# axiom_beta_interface_dummy_v0_7.net
KiCad netlist of a schematic drawn in EAGLE
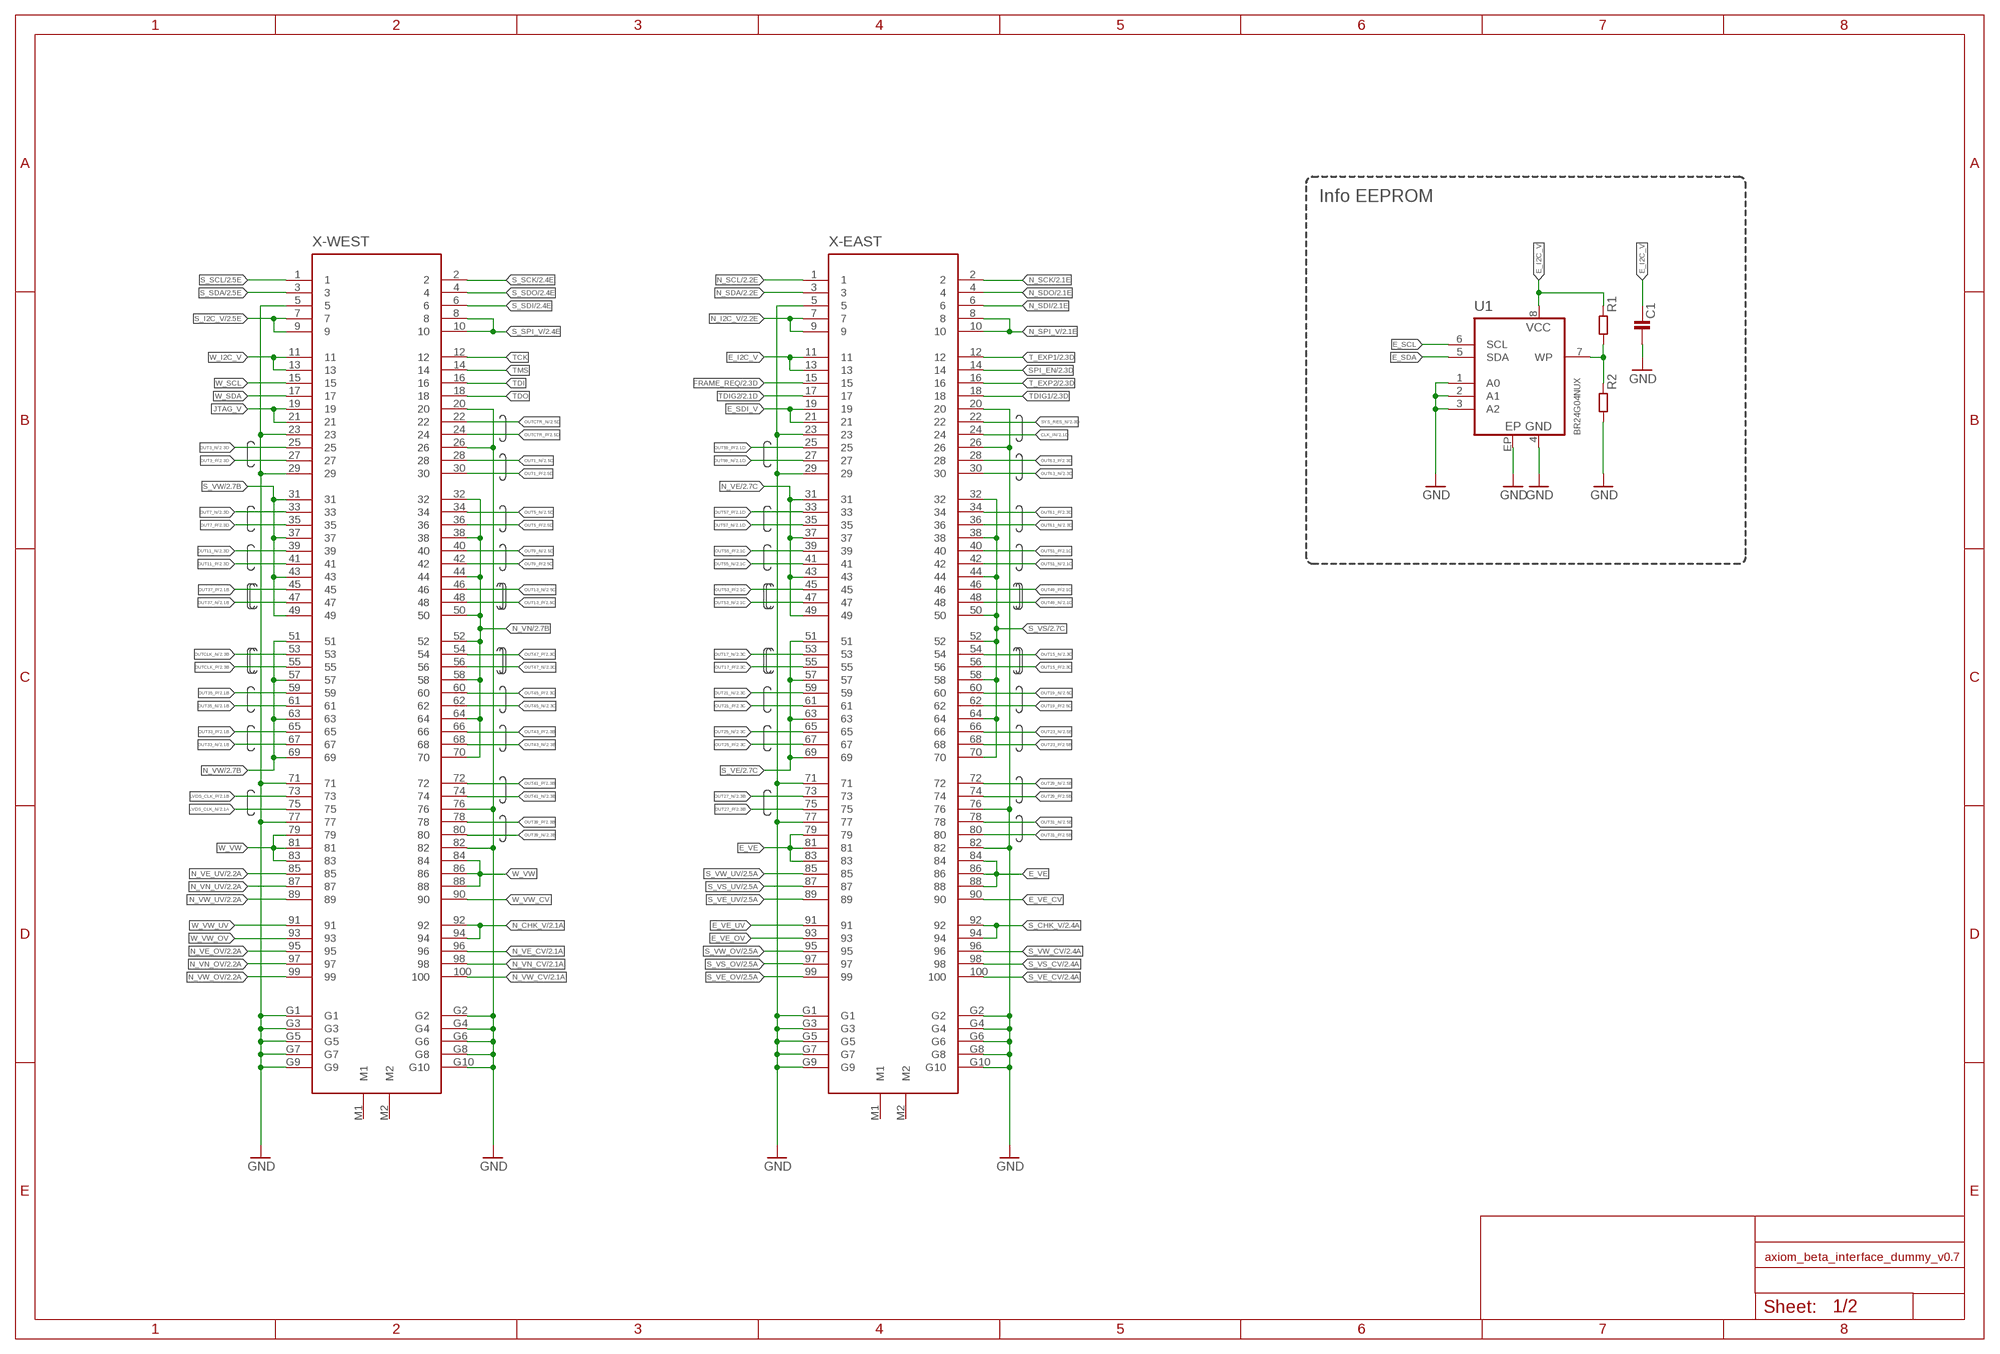
[diagram p0: schematic, sheet 1]
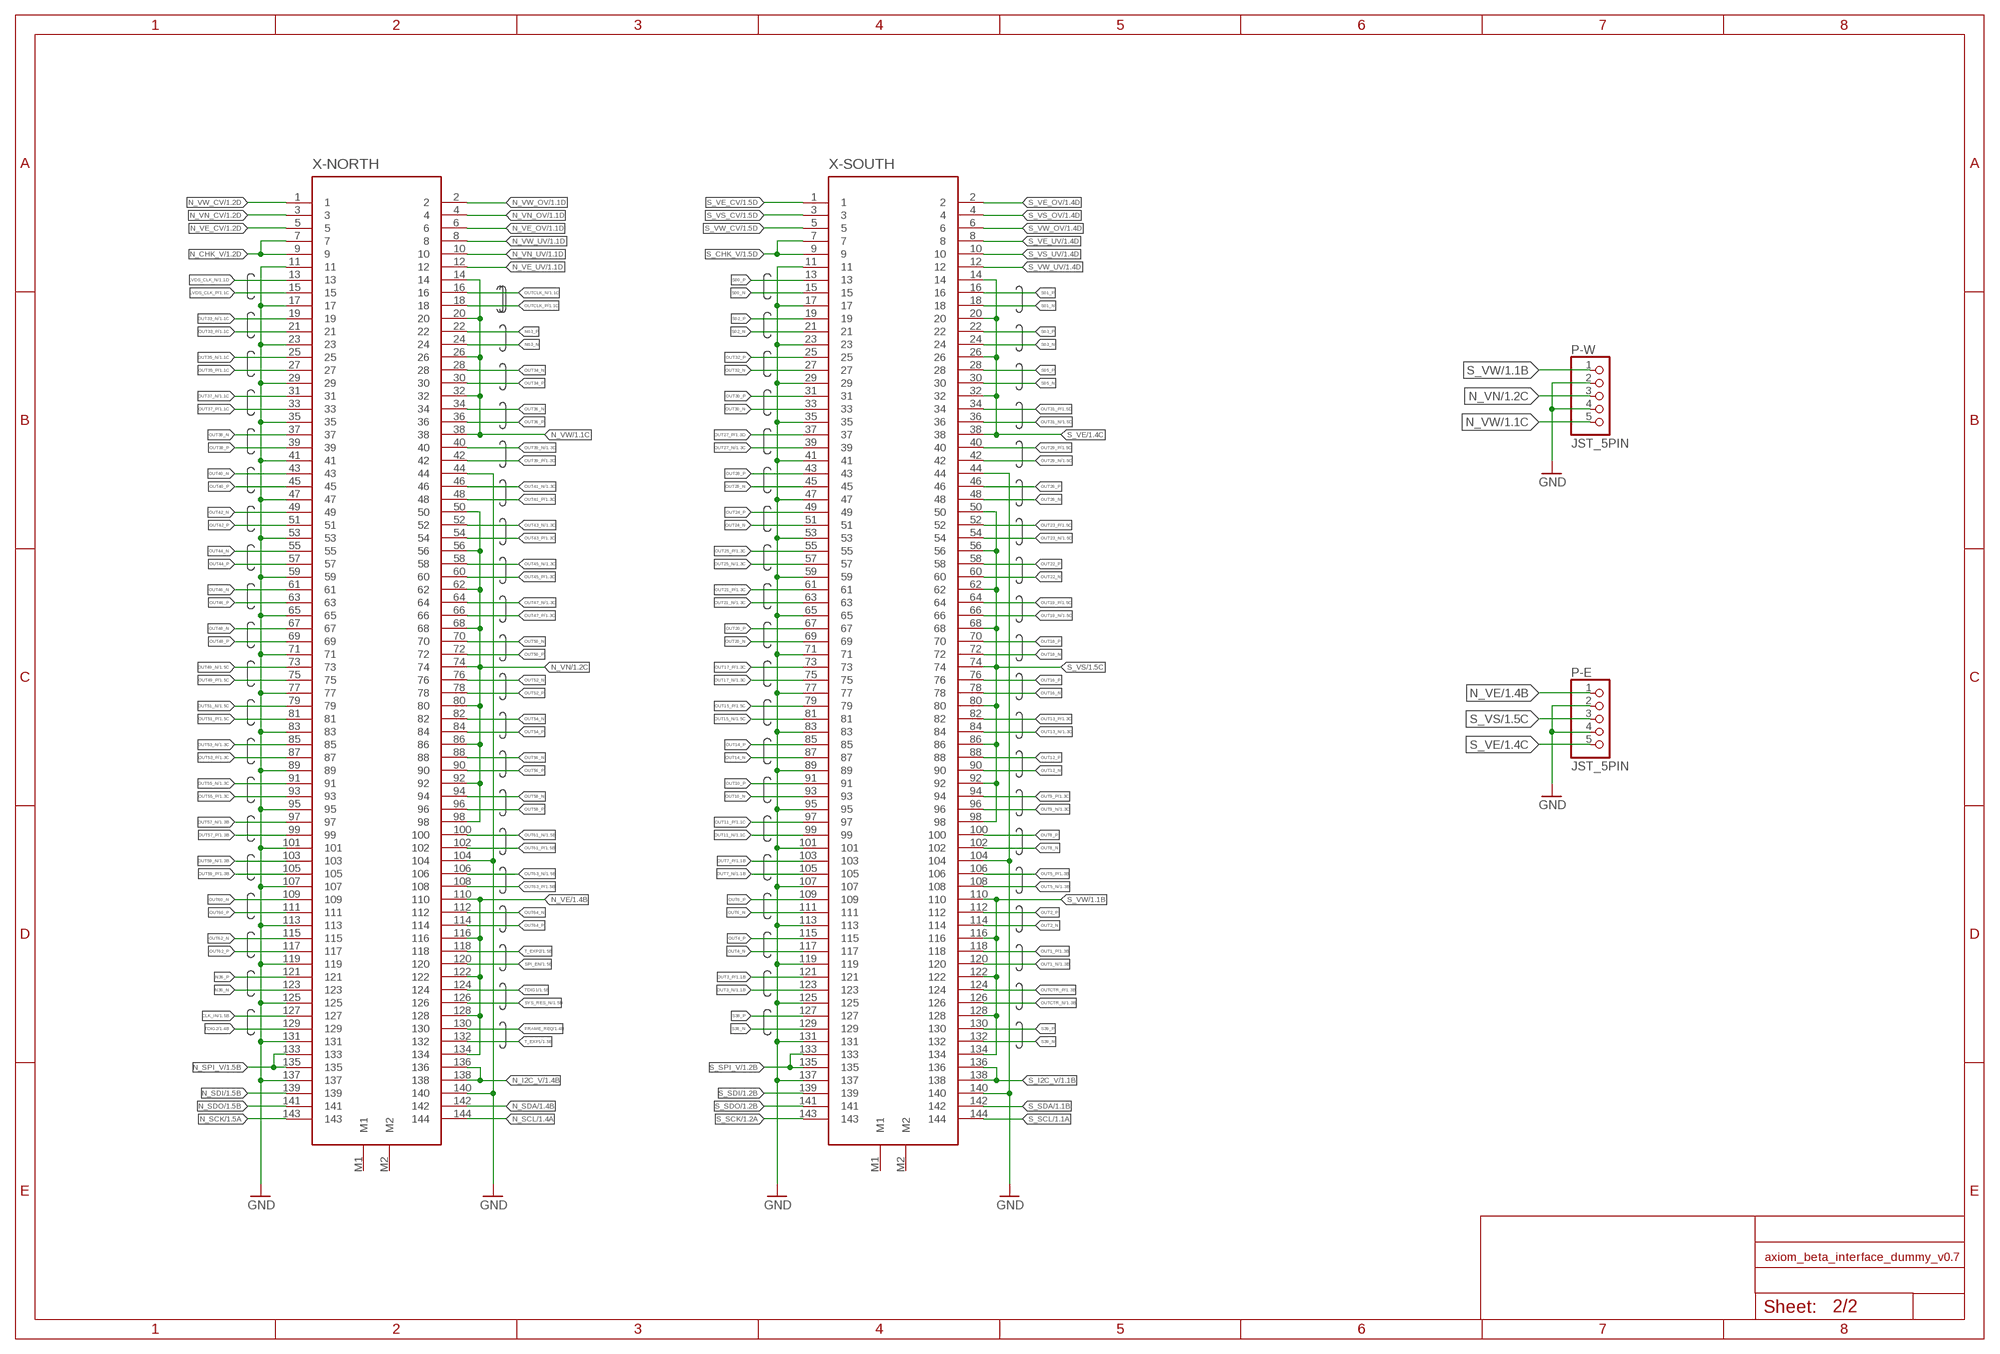
[diagram p1: schematic, sheet 2]

(export (version "E")
  (design (tool "Eeschema 10.0.6"))
  (components
    (comp (ref "P-E")
      (value "JST_5PIN")
      (footprint "eagle-import:JST-PH-5-SMT-RA")
      (libsource (lib "eagle-import") (part "JST_5PIN"))
    )
    (comp (ref "P-W")
      (value "JST_5PIN")
      (footprint "eagle-import:JST-PH-5-SMT-RA")
      (libsource (lib "eagle-import") (part "JST_5PIN"))
    )
    (comp (ref "X-NORTH")
      (value "FX10-144S")
      (footprint "eagle-import:FX10A-144S")
      (libsource (lib "eagle-import") (part "FX10-144S"))
    )
    (comp (ref "X-SOUTH")
      (value "FX10-144S")
      (footprint "eagle-import:FX10A-144S")
      (libsource (lib "eagle-import") (part "FX10-144S"))
    )
    (comp (ref "C1")
      (value "C0402-B")
      (footprint "eagle-import:0402-B")
      (libsource (lib "eagle-import") (part "C0402-B"))
    )
    (comp (ref "R1")
      (value "R0402-B")
      (footprint "eagle-import:0402-B")
      (libsource (lib "eagle-import") (part "R0402-B"))
    )
    (comp (ref "R2")
      (value "R0402-B")
      (footprint "eagle-import:0402-B")
      (libsource (lib "eagle-import") (part "R0402-B"))
    )
    (comp (ref "U1")
      (value "BR24G04NUX")
      (footprint "eagle-import:DFN200X300X100-9N")
      (libsource (lib "eagle-import") (part "BR24G04NUX"))
    )
    (comp (ref "X-EAST")
      (value "FX10-100/10P")
      (footprint "eagle-import:FX10A-100P_10")
      (libsource (lib "eagle-import") (part "FX10-100/10P"))
    )
    (comp (ref "X-WEST")
      (value "FX10-100/10P")
      (footprint "eagle-import:FX10A-100P_10")
      (libsource (lib "eagle-import") (part "FX10-100/10P"))
    )
  )
  (nets
    (net (code "1") (name "CLK_IN") (class "Default")
      (node (ref "X-EAST") (pin "24") (pinfunction "24_24") (pintype "bidirectional"))
      (node (ref "X-NORTH") (pin "127") (pinfunction "127_127") (pintype "bidirectional"))
    )
    (net (code "2") (name "E_I2C_V") (class "Default")
      (node (ref "C1") (pin "1") (pinfunction "1_1") (pintype "passive"))
      (node (ref "R1") (pin "1") (pinfunction "1_1") (pintype "passive"))
      (node (ref "U1") (pin "8") (pinfunction "VCC_8") (pintype "power_in"))
      (node (ref "X-EAST") (pin "11") (pinfunction "11_11") (pintype "bidirectional"))
      (node (ref "X-EAST") (pin "13") (pinfunction "13_13") (pintype "bidirectional"))
    )
    (net (code "3") (name "E_SCL") (class "Default")
      (node (ref "U1") (pin "6") (pinfunction "SCL_6") (pintype "input"))
    )
    (net (code "4") (name "E_SDA") (class "Default")
      (node (ref "U1") (pin "5") (pinfunction "SDA_5") (pintype "bidirectional"))
    )
    (net (code "5") (name "E_SDI_V") (class "Default")
      (node (ref "X-EAST") (pin "19") (pinfunction "19_19") (pintype "bidirectional"))
      (node (ref "X-EAST") (pin "21") (pinfunction "21_21") (pintype "bidirectional"))
    )
    (net (code "6") (name "E_VE") (class "Default")
      (node (ref "X-EAST") (pin "79") (pinfunction "79_79") (pintype "bidirectional"))
      (node (ref "X-EAST") (pin "81") (pinfunction "81_81") (pintype "bidirectional"))
      (node (ref "X-EAST") (pin "83") (pinfunction "83_83") (pintype "bidirectional"))
      (node (ref "X-EAST") (pin "84") (pinfunction "84_84") (pintype "bidirectional"))
      (node (ref "X-EAST") (pin "86") (pinfunction "86_86") (pintype "bidirectional"))
      (node (ref "X-EAST") (pin "88") (pinfunction "88_88") (pintype "bidirectional"))
    )
    (net (code "7") (name "E_VE_CV") (class "Default")
      (node (ref "X-EAST") (pin "90") (pinfunction "90_90") (pintype "bidirectional"))
    )
    (net (code "8") (name "E_VE_OV") (class "Default")
      (node (ref "X-EAST") (pin "93") (pinfunction "93_93") (pintype "bidirectional"))
    )
    (net (code "9") (name "E_VE_UV") (class "Default")
      (node (ref "X-EAST") (pin "91") (pinfunction "91_91") (pintype "bidirectional"))
    )
    (net (code "10") (name "FRAME_REQ") (class "Default")
      (node (ref "X-EAST") (pin "15") (pinfunction "15_15") (pintype "bidirectional"))
      (node (ref "X-NORTH") (pin "130") (pinfunction "130_130") (pintype "bidirectional"))
    )
    (net (code "11") (name "GND") (class "Default")
      (node (ref "C1") (pin "2") (pinfunction "2_2") (pintype "passive"))
      (node (ref "P-E") (pin "2") (pinfunction "2_2") (pintype "passive"))
      (node (ref "P-E") (pin "4") (pinfunction "4_4") (pintype "passive"))
      (node (ref "P-W") (pin "2") (pinfunction "2_2") (pintype "passive"))
      (node (ref "P-W") (pin "4") (pinfunction "4_4") (pintype "passive"))
      (node (ref "R2") (pin "2") (pinfunction "2_2") (pintype "passive"))
      (node (ref "U1") (pin "1") (pinfunction "A0_1") (pintype "input"))
      (node (ref "U1") (pin "2") (pinfunction "A1_2") (pintype "input"))
      (node (ref "U1") (pin "3") (pinfunction "A2_3") (pintype "input"))
      (node (ref "U1") (pin "4") (pinfunction "GND_4") (pintype "passive"))
      (node (ref "U1") (pin "EP") (pinfunction "EP_EP") (pintype "passive"))
      (node (ref "X-EAST") (pin "20") (pinfunction "20_20") (pintype "bidirectional"))
      (node (ref "X-EAST") (pin "23") (pinfunction "23_23") (pintype "bidirectional"))
      (node (ref "X-EAST") (pin "26") (pinfunction "26_26") (pintype "bidirectional"))
      (node (ref "X-EAST") (pin "29") (pinfunction "29_29") (pintype "bidirectional"))
      (node (ref "X-EAST") (pin "5") (pinfunction "5_5") (pintype "bidirectional"))
      (node (ref "X-EAST") (pin "71") (pinfunction "71_71") (pintype "bidirectional"))
      (node (ref "X-EAST") (pin "76") (pinfunction "76_76") (pintype "bidirectional"))
      (node (ref "X-EAST") (pin "77") (pinfunction "77_77") (pintype "bidirectional"))
      (node (ref "X-EAST") (pin "82") (pinfunction "82_82") (pintype "bidirectional"))
      (node (ref "X-EAST") (pin "G1") (pinfunction "G1_G1") (pintype "bidirectional"))
      (node (ref "X-EAST") (pin "G10") (pinfunction "G10_G10") (pintype "bidirectional"))
      (node (ref "X-EAST") (pin "G2") (pinfunction "G2_G2") (pintype "bidirectional"))
      (node (ref "X-EAST") (pin "G3") (pinfunction "G3_G3") (pintype "bidirectional"))
      (node (ref "X-EAST") (pin "G4") (pinfunction "G4_G4") (pintype "bidirectional"))
      (node (ref "X-EAST") (pin "G5") (pinfunction "G5_G5") (pintype "bidirectional"))
      (node (ref "X-EAST") (pin "G6") (pinfunction "G6_G6") (pintype "bidirectional"))
      (node (ref "X-EAST") (pin "G7") (pinfunction "G7_G7") (pintype "bidirectional"))
      (node (ref "X-EAST") (pin "G8") (pinfunction "G8_G8") (pintype "bidirectional"))
      (node (ref "X-EAST") (pin "G9") (pinfunction "G9_G9") (pintype "bidirectional"))
      (node (ref "X-NORTH") (pin "101") (pinfunction "101_101") (pintype "bidirectional"))
      (node (ref "X-NORTH") (pin "104") (pinfunction "104_104") (pintype "bidirectional"))
      (node (ref "X-NORTH") (pin "107") (pinfunction "107_107") (pintype "bidirectional"))
      (node (ref "X-NORTH") (pin "11") (pinfunction "11_11") (pintype "bidirectional"))
      (node (ref "X-NORTH") (pin "113") (pinfunction "113_113") (pintype "bidirectional"))
      (node (ref "X-NORTH") (pin "119") (pinfunction "119_119") (pintype "bidirectional"))
      (node (ref "X-NORTH") (pin "125") (pinfunction "125_125") (pintype "bidirectional"))
      (node (ref "X-NORTH") (pin "131") (pinfunction "131_131") (pintype "bidirectional"))
      (node (ref "X-NORTH") (pin "137") (pinfunction "137_137") (pintype "bidirectional"))
      (node (ref "X-NORTH") (pin "140") (pinfunction "140_140") (pintype "bidirectional"))
      (node (ref "X-NORTH") (pin "17") (pinfunction "17_17") (pintype "bidirectional"))
      (node (ref "X-NORTH") (pin "23") (pinfunction "23_23") (pintype "bidirectional"))
      (node (ref "X-NORTH") (pin "29") (pinfunction "29_29") (pintype "bidirectional"))
      (node (ref "X-NORTH") (pin "35") (pinfunction "35_35") (pintype "bidirectional"))
      (node (ref "X-NORTH") (pin "41") (pinfunction "41_41") (pintype "bidirectional"))
      (node (ref "X-NORTH") (pin "44") (pinfunction "44_44") (pintype "bidirectional"))
      (node (ref "X-NORTH") (pin "47") (pinfunction "47_47") (pintype "bidirectional"))
      (node (ref "X-NORTH") (pin "53") (pinfunction "53_53") (pintype "bidirectional"))
      (node (ref "X-NORTH") (pin "59") (pinfunction "59_59") (pintype "bidirectional"))
      (node (ref "X-NORTH") (pin "65") (pinfunction "65_65") (pintype "bidirectional"))
      (node (ref "X-NORTH") (pin "71") (pinfunction "71_71") (pintype "bidirectional"))
      (node (ref "X-NORTH") (pin "77") (pinfunction "77_77") (pintype "bidirectional"))
      (node (ref "X-NORTH") (pin "83") (pinfunction "83_83") (pintype "bidirectional"))
      (node (ref "X-NORTH") (pin "89") (pinfunction "89_89") (pintype "bidirectional"))
      (node (ref "X-NORTH") (pin "95") (pinfunction "95_95") (pintype "bidirectional"))
      (node (ref "X-SOUTH") (pin "101") (pinfunction "101_101") (pintype "bidirectional"))
      (node (ref "X-SOUTH") (pin "104") (pinfunction "104_104") (pintype "bidirectional"))
      (node (ref "X-SOUTH") (pin "107") (pinfunction "107_107") (pintype "bidirectional"))
      (node (ref "X-SOUTH") (pin "11") (pinfunction "11_11") (pintype "bidirectional"))
      (node (ref "X-SOUTH") (pin "113") (pinfunction "113_113") (pintype "bidirectional"))
      (node (ref "X-SOUTH") (pin "119") (pinfunction "119_119") (pintype "bidirectional"))
      (node (ref "X-SOUTH") (pin "125") (pinfunction "125_125") (pintype "bidirectional"))
      (node (ref "X-SOUTH") (pin "131") (pinfunction "131_131") (pintype "bidirectional"))
      (node (ref "X-SOUTH") (pin "137") (pinfunction "137_137") (pintype "bidirectional"))
      (node (ref "X-SOUTH") (pin "140") (pinfunction "140_140") (pintype "bidirectional"))
      (node (ref "X-SOUTH") (pin "17") (pinfunction "17_17") (pintype "bidirectional"))
      (node (ref "X-SOUTH") (pin "23") (pinfunction "23_23") (pintype "bidirectional"))
      (node (ref "X-SOUTH") (pin "29") (pinfunction "29_29") (pintype "bidirectional"))
      (node (ref "X-SOUTH") (pin "35") (pinfunction "35_35") (pintype "bidirectional"))
      (node (ref "X-SOUTH") (pin "41") (pinfunction "41_41") (pintype "bidirectional"))
      (node (ref "X-SOUTH") (pin "44") (pinfunction "44_44") (pintype "bidirectional"))
      (node (ref "X-SOUTH") (pin "47") (pinfunction "47_47") (pintype "bidirectional"))
      (node (ref "X-SOUTH") (pin "53") (pinfunction "53_53") (pintype "bidirectional"))
      (node (ref "X-SOUTH") (pin "59") (pinfunction "59_59") (pintype "bidirectional"))
      (node (ref "X-SOUTH") (pin "65") (pinfunction "65_65") (pintype "bidirectional"))
      (node (ref "X-SOUTH") (pin "71") (pinfunction "71_71") (pintype "bidirectional"))
      (node (ref "X-SOUTH") (pin "77") (pinfunction "77_77") (pintype "bidirectional"))
      (node (ref "X-SOUTH") (pin "83") (pinfunction "83_83") (pintype "bidirectional"))
      (node (ref "X-SOUTH") (pin "89") (pinfunction "89_89") (pintype "bidirectional"))
      (node (ref "X-SOUTH") (pin "95") (pinfunction "95_95") (pintype "bidirectional"))
      (node (ref "X-WEST") (pin "20") (pinfunction "20_20") (pintype "bidirectional"))
      (node (ref "X-WEST") (pin "23") (pinfunction "23_23") (pintype "bidirectional"))
      (node (ref "X-WEST") (pin "26") (pinfunction "26_26") (pintype "bidirectional"))
      (node (ref "X-WEST") (pin "29") (pinfunction "29_29") (pintype "bidirectional"))
      (node (ref "X-WEST") (pin "5") (pinfunction "5_5") (pintype "bidirectional"))
      (node (ref "X-WEST") (pin "71") (pinfunction "71_71") (pintype "bidirectional"))
      (node (ref "X-WEST") (pin "76") (pinfunction "76_76") (pintype "bidirectional"))
      (node (ref "X-WEST") (pin "77") (pinfunction "77_77") (pintype "bidirectional"))
      (node (ref "X-WEST") (pin "82") (pinfunction "82_82") (pintype "bidirectional"))
      (node (ref "X-WEST") (pin "G1") (pinfunction "G1_G1") (pintype "bidirectional"))
      (node (ref "X-WEST") (pin "G10") (pinfunction "G10_G10") (pintype "bidirectional"))
      (node (ref "X-WEST") (pin "G2") (pinfunction "G2_G2") (pintype "bidirectional"))
      (node (ref "X-WEST") (pin "G3") (pinfunction "G3_G3") (pintype "bidirectional"))
      (node (ref "X-WEST") (pin "G4") (pinfunction "G4_G4") (pintype "bidirectional"))
      (node (ref "X-WEST") (pin "G5") (pinfunction "G5_G5") (pintype "bidirectional"))
      (node (ref "X-WEST") (pin "G6") (pinfunction "G6_G6") (pintype "bidirectional"))
      (node (ref "X-WEST") (pin "G7") (pinfunction "G7_G7") (pintype "bidirectional"))
      (node (ref "X-WEST") (pin "G8") (pinfunction "G8_G8") (pintype "bidirectional"))
      (node (ref "X-WEST") (pin "G9") (pinfunction "G9_G9") (pintype "bidirectional"))
    )
    (net (code "12") (name "JTAG_V") (class "Default")
      (node (ref "X-WEST") (pin "19") (pinfunction "19_19") (pintype "bidirectional"))
      (node (ref "X-WEST") (pin "21") (pinfunction "21_21") (pintype "bidirectional"))
    )
    (net (code "13") (name "LVDS_CLK_N") (class "Default")
      (node (ref "X-NORTH") (pin "13") (pinfunction "13_13") (pintype "bidirectional"))
      (node (ref "X-WEST") (pin "75") (pinfunction "75_75") (pintype "bidirectional"))
    )
    (net (code "14") (name "LVDS_CLK_P") (class "Default")
      (node (ref "X-NORTH") (pin "15") (pinfunction "15_15") (pintype "bidirectional"))
      (node (ref "X-WEST") (pin "73") (pinfunction "73_73") (pintype "bidirectional"))
    )
    (net (code "15") (name "N03_N") (class "Default")
      (node (ref "X-NORTH") (pin "24") (pinfunction "24_24") (pintype "bidirectional"))
    )
    (net (code "16") (name "N03_P") (class "Default")
      (node (ref "X-NORTH") (pin "22") (pinfunction "22_22") (pintype "bidirectional"))
    )
    (net (code "17") (name "N36_N") (class "Default")
      (node (ref "X-NORTH") (pin "123") (pinfunction "123_123") (pintype "bidirectional"))
    )
    (net (code "18") (name "N36_P") (class "Default")
      (node (ref "X-NORTH") (pin "121") (pinfunction "121_121") (pintype "bidirectional"))
    )
    (net (code "19") (name "N_CHK_V") (class "Default")
      (node (ref "X-NORTH") (pin "7") (pinfunction "7_7") (pintype "bidirectional"))
      (node (ref "X-NORTH") (pin "9") (pinfunction "9_9") (pintype "bidirectional"))
      (node (ref "X-WEST") (pin "92") (pinfunction "92_92") (pintype "bidirectional"))
      (node (ref "X-WEST") (pin "94") (pinfunction "94_94") (pintype "bidirectional"))
    )
    (net (code "20") (name "N_I2C_V") (class "Default")
      (node (ref "X-EAST") (pin "7") (pinfunction "7_7") (pintype "bidirectional"))
      (node (ref "X-EAST") (pin "9") (pinfunction "9_9") (pintype "bidirectional"))
      (node (ref "X-NORTH") (pin "136") (pinfunction "136_136") (pintype "bidirectional"))
      (node (ref "X-NORTH") (pin "138") (pinfunction "138_138") (pintype "bidirectional"))
    )
    (net (code "21") (name "N_SCK") (class "Default")
      (node (ref "X-EAST") (pin "2") (pinfunction "2_2") (pintype "bidirectional"))
      (node (ref "X-NORTH") (pin "143") (pinfunction "143_143") (pintype "bidirectional"))
    )
    (net (code "22") (name "N_SCL") (class "Default")
      (node (ref "X-EAST") (pin "1") (pinfunction "1_1") (pintype "bidirectional"))
      (node (ref "X-NORTH") (pin "144") (pinfunction "144_144") (pintype "bidirectional"))
    )
    (net (code "23") (name "N_SDA") (class "Default")
      (node (ref "X-EAST") (pin "3") (pinfunction "3_3") (pintype "bidirectional"))
      (node (ref "X-NORTH") (pin "142") (pinfunction "142_142") (pintype "bidirectional"))
    )
    (net (code "24") (name "N_SDI") (class "Default")
      (node (ref "X-EAST") (pin "6") (pinfunction "6_6") (pintype "bidirectional"))
      (node (ref "X-NORTH") (pin "139") (pinfunction "139_139") (pintype "bidirectional"))
    )
    (net (code "25") (name "N_SDO") (class "Default")
      (node (ref "X-EAST") (pin "4") (pinfunction "4_4") (pintype "bidirectional"))
      (node (ref "X-NORTH") (pin "141") (pinfunction "141_141") (pintype "bidirectional"))
    )
    (net (code "26") (name "N_SPI_V") (class "Default")
      (node (ref "X-EAST") (pin "10") (pinfunction "10_10") (pintype "bidirectional"))
      (node (ref "X-EAST") (pin "8") (pinfunction "8_8") (pintype "bidirectional"))
      (node (ref "X-NORTH") (pin "133") (pinfunction "133_133") (pintype "bidirectional"))
      (node (ref "X-NORTH") (pin "135") (pinfunction "135_135") (pintype "bidirectional"))
    )
    (net (code "27") (name "N_VE") (class "Default")
      (node (ref "P-E") (pin "1") (pinfunction "1_1") (pintype "passive"))
      (node (ref "X-EAST") (pin "31") (pinfunction "31_31") (pintype "bidirectional"))
      (node (ref "X-EAST") (pin "37") (pinfunction "37_37") (pintype "bidirectional"))
      (node (ref "X-EAST") (pin "43") (pinfunction "43_43") (pintype "bidirectional"))
      (node (ref "X-EAST") (pin "49") (pinfunction "49_49") (pintype "bidirectional"))
      (node (ref "X-NORTH") (pin "110") (pinfunction "110_110") (pintype "bidirectional"))
      (node (ref "X-NORTH") (pin "116") (pinfunction "116_116") (pintype "bidirectional"))
      (node (ref "X-NORTH") (pin "122") (pinfunction "122_122") (pintype "bidirectional"))
      (node (ref "X-NORTH") (pin "128") (pinfunction "128_128") (pintype "bidirectional"))
      (node (ref "X-NORTH") (pin "134") (pinfunction "134_134") (pintype "bidirectional"))
    )
    (net (code "28") (name "N_VE_CV") (class "Default")
      (node (ref "X-NORTH") (pin "5") (pinfunction "5_5") (pintype "bidirectional"))
      (node (ref "X-WEST") (pin "96") (pinfunction "96_96") (pintype "bidirectional"))
    )
    (net (code "29") (name "N_VE_OV") (class "Default")
      (node (ref "X-NORTH") (pin "6") (pinfunction "6_6") (pintype "bidirectional"))
      (node (ref "X-WEST") (pin "95") (pinfunction "95_95") (pintype "bidirectional"))
    )
    (net (code "30") (name "N_VE_UV") (class "Default")
      (node (ref "X-NORTH") (pin "12") (pinfunction "12_12") (pintype "bidirectional"))
      (node (ref "X-WEST") (pin "85") (pinfunction "85_85") (pintype "bidirectional"))
    )
    (net (code "31") (name "N_VN") (class "Default")
      (node (ref "P-W") (pin "3") (pinfunction "3_3") (pintype "passive"))
      (node (ref "X-NORTH") (pin "50") (pinfunction "50_50") (pintype "bidirectional"))
      (node (ref "X-NORTH") (pin "56") (pinfunction "56_56") (pintype "bidirectional"))
      (node (ref "X-NORTH") (pin "62") (pinfunction "62_62") (pintype "bidirectional"))
      (node (ref "X-NORTH") (pin "68") (pinfunction "68_68") (pintype "bidirectional"))
      (node (ref "X-NORTH") (pin "74") (pinfunction "74_74") (pintype "bidirectional"))
      (node (ref "X-NORTH") (pin "80") (pinfunction "80_80") (pintype "bidirectional"))
      (node (ref "X-NORTH") (pin "86") (pinfunction "86_86") (pintype "bidirectional"))
      (node (ref "X-NORTH") (pin "92") (pinfunction "92_92") (pintype "bidirectional"))
      (node (ref "X-NORTH") (pin "98") (pinfunction "98_98") (pintype "bidirectional"))
      (node (ref "X-WEST") (pin "32") (pinfunction "32_32") (pintype "bidirectional"))
      (node (ref "X-WEST") (pin "38") (pinfunction "38_38") (pintype "bidirectional"))
      (node (ref "X-WEST") (pin "44") (pinfunction "44_44") (pintype "bidirectional"))
      (node (ref "X-WEST") (pin "50") (pinfunction "50_50") (pintype "bidirectional"))
      (node (ref "X-WEST") (pin "52") (pinfunction "52_52") (pintype "bidirectional"))
      (node (ref "X-WEST") (pin "58") (pinfunction "58_58") (pintype "bidirectional"))
      (node (ref "X-WEST") (pin "64") (pinfunction "64_64") (pintype "bidirectional"))
      (node (ref "X-WEST") (pin "70") (pinfunction "70_70") (pintype "bidirectional"))
    )
    (net (code "32") (name "N_VN_CV") (class "Default")
      (node (ref "X-NORTH") (pin "3") (pinfunction "3_3") (pintype "bidirectional"))
      (node (ref "X-WEST") (pin "98") (pinfunction "98_98") (pintype "bidirectional"))
    )
    (net (code "33") (name "N_VN_OV") (class "Default")
      (node (ref "X-NORTH") (pin "4") (pinfunction "4_4") (pintype "bidirectional"))
      (node (ref "X-WEST") (pin "97") (pinfunction "97_97") (pintype "bidirectional"))
    )
    (net (code "34") (name "N_VN_UV") (class "Default")
      (node (ref "X-NORTH") (pin "10") (pinfunction "10_10") (pintype "bidirectional"))
      (node (ref "X-WEST") (pin "87") (pinfunction "87_87") (pintype "bidirectional"))
    )
    (net (code "35") (name "N_VW") (class "Default")
      (node (ref "P-W") (pin "5") (pinfunction "5_5") (pintype "passive"))
      (node (ref "X-NORTH") (pin "14") (pinfunction "14_14") (pintype "bidirectional"))
      (node (ref "X-NORTH") (pin "20") (pinfunction "20_20") (pintype "bidirectional"))
      (node (ref "X-NORTH") (pin "26") (pinfunction "26_26") (pintype "bidirectional"))
      (node (ref "X-NORTH") (pin "32") (pinfunction "32_32") (pintype "bidirectional"))
      (node (ref "X-NORTH") (pin "38") (pinfunction "38_38") (pintype "bidirectional"))
      (node (ref "X-WEST") (pin "51") (pinfunction "51_51") (pintype "bidirectional"))
      (node (ref "X-WEST") (pin "57") (pinfunction "57_57") (pintype "bidirectional"))
      (node (ref "X-WEST") (pin "63") (pinfunction "63_63") (pintype "bidirectional"))
      (node (ref "X-WEST") (pin "69") (pinfunction "69_69") (pintype "bidirectional"))
    )
    (net (code "36") (name "N_VW_CV") (class "Default")
      (node (ref "X-NORTH") (pin "1") (pinfunction "1_1") (pintype "bidirectional"))
      (node (ref "X-WEST") (pin "100") (pinfunction "100_100") (pintype "bidirectional"))
    )
    (net (code "37") (name "N_VW_OV") (class "Default")
      (node (ref "X-NORTH") (pin "2") (pinfunction "2_2") (pintype "bidirectional"))
      (node (ref "X-WEST") (pin "99") (pinfunction "99_99") (pintype "bidirectional"))
    )
    (net (code "38") (name "N_VW_UV") (class "Default")
      (node (ref "X-NORTH") (pin "8") (pinfunction "8_8") (pintype "bidirectional"))
      (node (ref "X-WEST") (pin "89") (pinfunction "89_89") (pintype "bidirectional"))
    )
    (net (code "39") (name "Net-(U1-WP)") (class "Default")
      (node (ref "R1") (pin "2") (pinfunction "2_2") (pintype "passive"))
      (node (ref "R2") (pin "1") (pinfunction "1_1") (pintype "passive"))
      (node (ref "U1") (pin "7") (pinfunction "WP_7") (pintype "input"))
    )
    (net (code "40") (name "OUT1_N") (class "Default")
      (node (ref "X-SOUTH") (pin "120") (pinfunction "120_120") (pintype "bidirectional"))
      (node (ref "X-WEST") (pin "28") (pinfunction "28_28") (pintype "bidirectional"))
    )
    (net (code "41") (name "OUT1_P") (class "Default")
      (node (ref "X-SOUTH") (pin "118") (pinfunction "118_118") (pintype "bidirectional"))
      (node (ref "X-WEST") (pin "30") (pinfunction "30_30") (pintype "bidirectional"))
    )
    (net (code "42") (name "OUT2_N") (class "Default")
      (node (ref "X-SOUTH") (pin "114") (pinfunction "114_114") (pintype "bidirectional"))
    )
    (net (code "43") (name "OUT2_P") (class "Default")
      (node (ref "X-SOUTH") (pin "112") (pinfunction "112_112") (pintype "bidirectional"))
    )
    (net (code "44") (name "OUT3_N") (class "Default")
      (node (ref "X-SOUTH") (pin "123") (pinfunction "123_123") (pintype "bidirectional"))
      (node (ref "X-WEST") (pin "25") (pinfunction "25_25") (pintype "bidirectional"))
    )
    (net (code "45") (name "OUT3_P") (class "Default")
      (node (ref "X-SOUTH") (pin "121") (pinfunction "121_121") (pintype "bidirectional"))
      (node (ref "X-WEST") (pin "27") (pinfunction "27_27") (pintype "bidirectional"))
    )
    (net (code "46") (name "OUT4_N") (class "Default")
      (node (ref "X-SOUTH") (pin "117") (pinfunction "117_117") (pintype "bidirectional"))
    )
    (net (code "47") (name "OUT4_P") (class "Default")
      (node (ref "X-SOUTH") (pin "115") (pinfunction "115_115") (pintype "bidirectional"))
    )
    (net (code "48") (name "OUT5_N") (class "Default")
      (node (ref "X-SOUTH") (pin "108") (pinfunction "108_108") (pintype "bidirectional"))
      (node (ref "X-WEST") (pin "34") (pinfunction "34_34") (pintype "bidirectional"))
    )
    (net (code "49") (name "OUT5_P") (class "Default")
      (node (ref "X-SOUTH") (pin "106") (pinfunction "106_106") (pintype "bidirectional"))
      (node (ref "X-WEST") (pin "36") (pinfunction "36_36") (pintype "bidirectional"))
    )
    (net (code "50") (name "OUT6_N") (class "Default")
      (node (ref "X-SOUTH") (pin "111") (pinfunction "111_111") (pintype "bidirectional"))
    )
    (net (code "51") (name "OUT6_P") (class "Default")
      (node (ref "X-SOUTH") (pin "109") (pinfunction "109_109") (pintype "bidirectional"))
    )
    (net (code "52") (name "OUT7_N") (class "Default")
      (node (ref "X-SOUTH") (pin "105") (pinfunction "105_105") (pintype "bidirectional"))
      (node (ref "X-WEST") (pin "33") (pinfunction "33_33") (pintype "bidirectional"))
    )
    (net (code "53") (name "OUT7_P") (class "Default")
      (node (ref "X-SOUTH") (pin "103") (pinfunction "103_103") (pintype "bidirectional"))
      (node (ref "X-WEST") (pin "35") (pinfunction "35_35") (pintype "bidirectional"))
    )
    (net (code "54") (name "OUT8_N") (class "Default")
      (node (ref "X-SOUTH") (pin "102") (pinfunction "102_102") (pintype "bidirectional"))
    )
    (net (code "55") (name "OUT8_P") (class "Default")
      (node (ref "X-SOUTH") (pin "100") (pinfunction "100_100") (pintype "bidirectional"))
    )
    (net (code "56") (name "OUT9_N") (class "Default")
      (node (ref "X-SOUTH") (pin "96") (pinfunction "96_96") (pintype "bidirectional"))
      (node (ref "X-WEST") (pin "40") (pinfunction "40_40") (pintype "bidirectional"))
    )
    (net (code "57") (name "OUT9_P") (class "Default")
      (node (ref "X-SOUTH") (pin "94") (pinfunction "94_94") (pintype "bidirectional"))
      (node (ref "X-WEST") (pin "42") (pinfunction "42_42") (pintype "bidirectional"))
    )
    (net (code "58") (name "OUT10_N") (class "Default")
      (node (ref "X-SOUTH") (pin "93") (pinfunction "93_93") (pintype "bidirectional"))
    )
    (net (code "59") (name "OUT10_P") (class "Default")
      (node (ref "X-SOUTH") (pin "91") (pinfunction "91_91") (pintype "bidirectional"))
    )
    (net (code "60") (name "OUT11_N") (class "Default")
      (node (ref "X-SOUTH") (pin "99") (pinfunction "99_99") (pintype "bidirectional"))
      (node (ref "X-WEST") (pin "39") (pinfunction "39_39") (pintype "bidirectional"))
    )
    (net (code "61") (name "OUT11_P") (class "Default")
      (node (ref "X-SOUTH") (pin "97") (pinfunction "97_97") (pintype "bidirectional"))
      (node (ref "X-WEST") (pin "41") (pinfunction "41_41") (pintype "bidirectional"))
    )
    (net (code "62") (name "OUT12_N") (class "Default")
      (node (ref "X-SOUTH") (pin "90") (pinfunction "90_90") (pintype "bidirectional"))
    )
    (net (code "63") (name "OUT12_P") (class "Default")
      (node (ref "X-SOUTH") (pin "88") (pinfunction "88_88") (pintype "bidirectional"))
    )
    (net (code "64") (name "OUT13_N") (class "Default")
      (node (ref "X-SOUTH") (pin "84") (pinfunction "84_84") (pintype "bidirectional"))
      (node (ref "X-WEST") (pin "46") (pinfunction "46_46") (pintype "bidirectional"))
    )
    (net (code "65") (name "OUT13_P") (class "Default")
      (node (ref "X-SOUTH") (pin "82") (pinfunction "82_82") (pintype "bidirectional"))
      (node (ref "X-WEST") (pin "48") (pinfunction "48_48") (pintype "bidirectional"))
    )
    (net (code "66") (name "OUT14_N") (class "Default")
      (node (ref "X-SOUTH") (pin "87") (pinfunction "87_87") (pintype "bidirectional"))
    )
    (net (code "67") (name "OUT14_P") (class "Default")
      (node (ref "X-SOUTH") (pin "85") (pinfunction "85_85") (pintype "bidirectional"))
    )
    (net (code "68") (name "OUT15_N") (class "Default")
      (node (ref "X-EAST") (pin "54") (pinfunction "54_54") (pintype "bidirectional"))
      (node (ref "X-SOUTH") (pin "81") (pinfunction "81_81") (pintype "bidirectional"))
    )
    (net (code "69") (name "OUT15_P") (class "Default")
      (node (ref "X-EAST") (pin "56") (pinfunction "56_56") (pintype "bidirectional"))
      (node (ref "X-SOUTH") (pin "79") (pinfunction "79_79") (pintype "bidirectional"))
    )
    (net (code "70") (name "OUT16_N") (class "Default")
      (node (ref "X-SOUTH") (pin "78") (pinfunction "78_78") (pintype "bidirectional"))
    )
    (net (code "71") (name "OUT16_P") (class "Default")
      (node (ref "X-SOUTH") (pin "76") (pinfunction "76_76") (pintype "bidirectional"))
    )
    (net (code "72") (name "OUT17_N") (class "Default")
      (node (ref "X-EAST") (pin "53") (pinfunction "53_53") (pintype "bidirectional"))
      (node (ref "X-SOUTH") (pin "75") (pinfunction "75_75") (pintype "bidirectional"))
    )
    (net (code "73") (name "OUT17_P") (class "Default")
      (node (ref "X-EAST") (pin "55") (pinfunction "55_55") (pintype "bidirectional"))
      (node (ref "X-SOUTH") (pin "73") (pinfunction "73_73") (pintype "bidirectional"))
    )
    (net (code "74") (name "OUT18_N") (class "Default")
      (node (ref "X-SOUTH") (pin "72") (pinfunction "72_72") (pintype "bidirectional"))
    )
    (net (code "75") (name "OUT18_P") (class "Default")
      (node (ref "X-SOUTH") (pin "70") (pinfunction "70_70") (pintype "bidirectional"))
    )
    (net (code "76") (name "OUT19_N") (class "Default")
      (node (ref "X-EAST") (pin "60") (pinfunction "60_60") (pintype "bidirectional"))
      (node (ref "X-SOUTH") (pin "66") (pinfunction "66_66") (pintype "bidirectional"))
    )
    (net (code "77") (name "OUT19_P") (class "Default")
      (node (ref "X-EAST") (pin "62") (pinfunction "62_62") (pintype "bidirectional"))
      (node (ref "X-SOUTH") (pin "64") (pinfunction "64_64") (pintype "bidirectional"))
    )
    (net (code "78") (name "OUT20_N") (class "Default")
      (node (ref "X-SOUTH") (pin "69") (pinfunction "69_69") (pintype "bidirectional"))
    )
    (net (code "79") (name "OUT20_P") (class "Default")
      (node (ref "X-SOUTH") (pin "67") (pinfunction "67_67") (pintype "bidirectional"))
    )
    (net (code "80") (name "OUT21_N") (class "Default")
      (node (ref "X-EAST") (pin "59") (pinfunction "59_59") (pintype "bidirectional"))
      (node (ref "X-SOUTH") (pin "63") (pinfunction "63_63") (pintype "bidirectional"))
    )
    (net (code "81") (name "OUT21_P") (class "Default")
      (node (ref "X-EAST") (pin "61") (pinfunction "61_61") (pintype "bidirectional"))
      (node (ref "X-SOUTH") (pin "61") (pinfunction "61_61") (pintype "bidirectional"))
    )
    (net (code "82") (name "OUT22_N") (class "Default")
      (node (ref "X-SOUTH") (pin "60") (pinfunction "60_60") (pintype "bidirectional"))
    )
    (net (code "83") (name "OUT22_P") (class "Default")
      (node (ref "X-SOUTH") (pin "58") (pinfunction "58_58") (pintype "bidirectional"))
    )
    (net (code "84") (name "OUT23_N") (class "Default")
      (node (ref "X-EAST") (pin "66") (pinfunction "66_66") (pintype "bidirectional"))
      (node (ref "X-SOUTH") (pin "54") (pinfunction "54_54") (pintype "bidirectional"))
    )
    (net (code "85") (name "OUT23_P") (class "Default")
      (node (ref "X-EAST") (pin "68") (pinfunction "68_68") (pintype "bidirectional"))
      (node (ref "X-SOUTH") (pin "52") (pinfunction "52_52") (pintype "bidirectional"))
    )
    (net (code "86") (name "OUT24_N") (class "Default")
      (node (ref "X-SOUTH") (pin "51") (pinfunction "51_51") (pintype "bidirectional"))
    )
    (net (code "87") (name "OUT24_P") (class "Default")
      (node (ref "X-SOUTH") (pin "49") (pinfunction "49_49") (pintype "bidirectional"))
    )
    (net (code "88") (name "OUT25_N") (class "Default")
      (node (ref "X-EAST") (pin "65") (pinfunction "65_65") (pintype "bidirectional"))
      (node (ref "X-SOUTH") (pin "57") (pinfunction "57_57") (pintype "bidirectional"))
    )
    (net (code "89") (name "OUT25_P") (class "Default")
      (node (ref "X-EAST") (pin "67") (pinfunction "67_67") (pintype "bidirectional"))
      (node (ref "X-SOUTH") (pin "55") (pinfunction "55_55") (pintype "bidirectional"))
    )
    (net (code "90") (name "OUT26_N") (class "Default")
      (node (ref "X-SOUTH") (pin "48") (pinfunction "48_48") (pintype "bidirectional"))
    )
    (net (code "91") (name "OUT26_P") (class "Default")
      (node (ref "X-SOUTH") (pin "46") (pinfunction "46_46") (pintype "bidirectional"))
    )
    (net (code "92") (name "OUT27_N") (class "Default")
      (node (ref "X-EAST") (pin "73") (pinfunction "73_73") (pintype "bidirectional"))
      (node (ref "X-SOUTH") (pin "39") (pinfunction "39_39") (pintype "bidirectional"))
    )
    (net (code "93") (name "OUT27_P") (class "Default")
      (node (ref "X-EAST") (pin "75") (pinfunction "75_75") (pintype "bidirectional"))
      (node (ref "X-SOUTH") (pin "37") (pinfunction "37_37") (pintype "bidirectional"))
    )
    (net (code "94") (name "OUT28_N") (class "Default")
      (node (ref "X-SOUTH") (pin "45") (pinfunction "45_45") (pintype "bidirectional"))
    )
    (net (code "95") (name "OUT28_P") (class "Default")
      (node (ref "X-SOUTH") (pin "43") (pinfunction "43_43") (pintype "bidirectional"))
    )
    (net (code "96") (name "OUT29_N") (class "Default")
      (node (ref "X-EAST") (pin "72") (pinfunction "72_72") (pintype "bidirectional"))
      (node (ref "X-SOUTH") (pin "42") (pinfunction "42_42") (pintype "bidirectional"))
    )
    (net (code "97") (name "OUT29_P") (class "Default")
      (node (ref "X-EAST") (pin "74") (pinfunction "74_74") (pintype "bidirectional"))
      (node (ref "X-SOUTH") (pin "40") (pinfunction "40_40") (pintype "bidirectional"))
    )
    (net (code "98") (name "OUT30_N") (class "Default")
      (node (ref "X-SOUTH") (pin "33") (pinfunction "33_33") (pintype "bidirectional"))
    )
    (net (code "99") (name "OUT30_P") (class "Default")
      (node (ref "X-SOUTH") (pin "31") (pinfunction "31_31") (pintype "bidirectional"))
    )
    (net (code "100") (name "OUT31_N") (class "Default")
      (node (ref "X-EAST") (pin "78") (pinfunction "78_78") (pintype "bidirectional"))
      (node (ref "X-SOUTH") (pin "36") (pinfunction "36_36") (pintype "bidirectional"))
    )
    (net (code "101") (name "OUT31_P") (class "Default")
      (node (ref "X-EAST") (pin "80") (pinfunction "80_80") (pintype "bidirectional"))
      (node (ref "X-SOUTH") (pin "34") (pinfunction "34_34") (pintype "bidirectional"))
    )
    (net (code "102") (name "OUT32_N") (class "Default")
      (node (ref "X-SOUTH") (pin "27") (pinfunction "27_27") (pintype "bidirectional"))
    )
    (net (code "103") (name "OUT32_P") (class "Default")
      (node (ref "X-SOUTH") (pin "25") (pinfunction "25_25") (pintype "bidirectional"))
    )
    (net (code "104") (name "OUT33_N") (class "Default")
      (node (ref "X-NORTH") (pin "19") (pinfunction "19_19") (pintype "bidirectional"))
      (node (ref "X-WEST") (pin "67") (pinfunction "67_67") (pintype "bidirectional"))
    )
    (net (code "105") (name "OUT33_P") (class "Default")
      (node (ref "X-NORTH") (pin "21") (pinfunction "21_21") (pintype "bidirectional"))
      (node (ref "X-WEST") (pin "65") (pinfunction "65_65") (pintype "bidirectional"))
    )
    (net (code "106") (name "OUT34_N") (class "Default")
      (node (ref "X-NORTH") (pin "28") (pinfunction "28_28") (pintype "bidirectional"))
    )
    (net (code "107") (name "OUT34_P") (class "Default")
      (node (ref "X-NORTH") (pin "30") (pinfunction "30_30") (pintype "bidirectional"))
    )
    (net (code "108") (name "OUT35_N") (class "Default")
      (node (ref "X-NORTH") (pin "25") (pinfunction "25_25") (pintype "bidirectional"))
      (node (ref "X-WEST") (pin "61") (pinfunction "61_61") (pintype "bidirectional"))
    )
    (net (code "109") (name "OUT35_P") (class "Default")
      (node (ref "X-NORTH") (pin "27") (pinfunction "27_27") (pintype "bidirectional"))
      (node (ref "X-WEST") (pin "59") (pinfunction "59_59") (pintype "bidirectional"))
    )
    (net (code "110") (name "OUT36_N") (class "Default")
      (node (ref "X-NORTH") (pin "34") (pinfunction "34_34") (pintype "bidirectional"))
    )
    (net (code "111") (name "OUT36_P") (class "Default")
      (node (ref "X-NORTH") (pin "36") (pinfunction "36_36") (pintype "bidirectional"))
    )
    (net (code "112") (name "OUT37_N") (class "Default")
      (node (ref "X-NORTH") (pin "31") (pinfunction "31_31") (pintype "bidirectional"))
      (node (ref "X-WEST") (pin "47") (pinfunction "47_47") (pintype "bidirectional"))
    )
    (net (code "113") (name "OUT37_P") (class "Default")
      (node (ref "X-NORTH") (pin "33") (pinfunction "33_33") (pintype "bidirectional"))
      (node (ref "X-WEST") (pin "45") (pinfunction "45_45") (pintype "bidirectional"))
    )
    (net (code "114") (name "OUT38_N") (class "Default")
      (node (ref "X-NORTH") (pin "37") (pinfunction "37_37") (pintype "bidirectional"))
    )
    (net (code "115") (name "OUT38_P") (class "Default")
      (node (ref "X-NORTH") (pin "39") (pinfunction "39_39") (pintype "bidirectional"))
    )
    (net (code "116") (name "OUT39_N") (class "Default")
      (node (ref "X-NORTH") (pin "40") (pinfunction "40_40") (pintype "bidirectional"))
      (node (ref "X-WEST") (pin "80") (pinfunction "80_80") (pintype "bidirectional"))
    )
    (net (code "117") (name "OUT39_P") (class "Default")
      (node (ref "X-NORTH") (pin "42") (pinfunction "42_42") (pintype "bidirectional"))
      (node (ref "X-WEST") (pin "78") (pinfunction "78_78") (pintype "bidirectional"))
    )
    (net (code "118") (name "OUT40_N") (class "Default")
      (node (ref "X-NORTH") (pin "43") (pinfunction "43_43") (pintype "bidirectional"))
    )
    (net (code "119") (name "OUT40_P") (class "Default")
      (node (ref "X-NORTH") (pin "45") (pinfunction "45_45") (pintype "bidirectional"))
    )
    (net (code "120") (name "OUT41_N") (class "Default")
      (node (ref "X-NORTH") (pin "46") (pinfunction "46_46") (pintype "bidirectional"))
      (node (ref "X-WEST") (pin "74") (pinfunction "74_74") (pintype "bidirectional"))
    )
    (net (code "121") (name "OUT41_P") (class "Default")
      (node (ref "X-NORTH") (pin "48") (pinfunction "48_48") (pintype "bidirectional"))
      (node (ref "X-WEST") (pin "72") (pinfunction "72_72") (pintype "bidirectional"))
    )
    (net (code "122") (name "OUT42_N") (class "Default")
      (node (ref "X-NORTH") (pin "49") (pinfunction "49_49") (pintype "bidirectional"))
    )
    (net (code "123") (name "OUT42_P") (class "Default")
      (node (ref "X-NORTH") (pin "51") (pinfunction "51_51") (pintype "bidirectional"))
    )
    (net (code "124") (name "OUT43_N") (class "Default")
      (node (ref "X-NORTH") (pin "52") (pinfunction "52_52") (pintype "bidirectional"))
      (node (ref "X-WEST") (pin "68") (pinfunction "68_68") (pintype "bidirectional"))
    )
    (net (code "125") (name "OUT43_P") (class "Default")
      (node (ref "X-NORTH") (pin "54") (pinfunction "54_54") (pintype "bidirectional"))
      (node (ref "X-WEST") (pin "66") (pinfunction "66_66") (pintype "bidirectional"))
    )
    (net (code "126") (name "OUT44_N") (class "Default")
      (node (ref "X-NORTH") (pin "55") (pinfunction "55_55") (pintype "bidirectional"))
    )
    (net (code "127") (name "OUT44_P") (class "Default")
      (node (ref "X-NORTH") (pin "57") (pinfunction "57_57") (pintype "bidirectional"))
    )
    (net (code "128") (name "OUT45_N") (class "Default")
      (node (ref "X-NORTH") (pin "58") (pinfunction "58_58") (pintype "bidirectional"))
      (node (ref "X-WEST") (pin "62") (pinfunction "62_62") (pintype "bidirectional"))
    )
    (net (code "129") (name "OUT45_P") (class "Default")
      (node (ref "X-NORTH") (pin "60") (pinfunction "60_60") (pintype "bidirectional"))
      (node (ref "X-WEST") (pin "60") (pinfunction "60_60") (pintype "bidirectional"))
    )
    (net (code "130") (name "OUT46_N") (class "Default")
      (node (ref "X-NORTH") (pin "61") (pinfunction "61_61") (pintype "bidirectional"))
    )
    (net (code "131") (name "OUT46_P") (class "Default")
      (node (ref "X-NORTH") (pin "63") (pinfunction "63_63") (pintype "bidirectional"))
    )
    (net (code "132") (name "OUT47_N") (class "Default")
      (node (ref "X-NORTH") (pin "64") (pinfunction "64_64") (pintype "bidirectional"))
      (node (ref "X-WEST") (pin "56") (pinfunction "56_56") (pintype "bidirectional"))
    )
    (net (code "133") (name "OUT47_P") (class "Default")
      (node (ref "X-NORTH") (pin "66") (pinfunction "66_66") (pintype "bidirectional"))
      (node (ref "X-WEST") (pin "54") (pinfunction "54_54") (pintype "bidirectional"))
    )
    (net (code "134") (name "OUT48_N") (class "Default")
      (node (ref "X-NORTH") (pin "67") (pinfunction "67_67") (pintype "bidirectional"))
    )
    (net (code "135") (name "OUT48_P") (class "Default")
      (node (ref "X-NORTH") (pin "69") (pinfunction "69_69") (pintype "bidirectional"))
    )
    (net (code "136") (name "OUT49_N") (class "Default")
      (node (ref "X-EAST") (pin "48") (pinfunction "48_48") (pintype "bidirectional"))
      (node (ref "X-NORTH") (pin "73") (pinfunction "73_73") (pintype "bidirectional"))
    )
    (net (code "137") (name "OUT49_P") (class "Default")
      (node (ref "X-EAST") (pin "46") (pinfunction "46_46") (pintype "bidirectional"))
      (node (ref "X-NORTH") (pin "75") (pinfunction "75_75") (pintype "bidirectional"))
    )
    (net (code "138") (name "OUT50_N") (class "Default")
      (node (ref "X-NORTH") (pin "70") (pinfunction "70_70") (pintype "bidirectional"))
    )
    (net (code "139") (name "OUT50_P") (class "Default")
      (node (ref "X-NORTH") (pin "72") (pinfunction "72_72") (pintype "bidirectional"))
    )
    (net (code "140") (name "OUT51_N") (class "Default")
      (node (ref "X-EAST") (pin "42") (pinfunction "42_42") (pintype "bidirectional"))
      (node (ref "X-NORTH") (pin "79") (pinfunction "79_79") (pintype "bidirectional"))
    )
    (net (code "141") (name "OUT51_P") (class "Default")
      (node (ref "X-EAST") (pin "40") (pinfunction "40_40") (pintype "bidirectional"))
      (node (ref "X-NORTH") (pin "81") (pinfunction "81_81") (pintype "bidirectional"))
    )
    (net (code "142") (name "OUT52_N") (class "Default")
      (node (ref "X-NORTH") (pin "76") (pinfunction "76_76") (pintype "bidirectional"))
    )
    (net (code "143") (name "OUT52_P") (class "Default")
      (node (ref "X-NORTH") (pin "78") (pinfunction "78_78") (pintype "bidirectional"))
    )
    (net (code "144") (name "OUT53_N") (class "Default")
      (node (ref "X-EAST") (pin "47") (pinfunction "47_47") (pintype "bidirectional"))
      (node (ref "X-NORTH") (pin "85") (pinfunction "85_85") (pintype "bidirectional"))
    )
    (net (code "145") (name "OUT53_P") (class "Default")
      (node (ref "X-EAST") (pin "45") (pinfunction "45_45") (pintype "bidirectional"))
      (node (ref "X-NORTH") (pin "87") (pinfunction "87_87") (pintype "bidirectional"))
    )
    (net (code "146") (name "OUT54_N") (class "Default")
      (node (ref "X-NORTH") (pin "82") (pinfunction "82_82") (pintype "bidirectional"))
    )
    (net (code "147") (name "OUT54_P") (class "Default")
      (node (ref "X-NORTH") (pin "84") (pinfunction "84_84") (pintype "bidirectional"))
    )
    (net (code "148") (name "OUT55_N") (class "Default")
      (node (ref "X-EAST") (pin "41") (pinfunction "41_41") (pintype "bidirectional"))
      (node (ref "X-NORTH") (pin "91") (pinfunction "91_91") (pintype "bidirectional"))
    )
    (net (code "149") (name "OUT55_P") (class "Default")
      (node (ref "X-EAST") (pin "39") (pinfunction "39_39") (pintype "bidirectional"))
      (node (ref "X-NORTH") (pin "93") (pinfunction "93_93") (pintype "bidirectional"))
    )
    (net (code "150") (name "OUT56_N") (class "Default")
      (node (ref "X-NORTH") (pin "88") (pinfunction "88_88") (pintype "bidirectional"))
    )
    (net (code "151") (name "OUT56_P") (class "Default")
      (node (ref "X-NORTH") (pin "90") (pinfunction "90_90") (pintype "bidirectional"))
    )
    (net (code "152") (name "OUT57_N") (class "Default")
      (node (ref "X-EAST") (pin "35") (pinfunction "35_35") (pintype "bidirectional"))
      (node (ref "X-NORTH") (pin "97") (pinfunction "97_97") (pintype "bidirectional"))
    )
    (net (code "153") (name "OUT57_P") (class "Default")
      (node (ref "X-EAST") (pin "33") (pinfunction "33_33") (pintype "bidirectional"))
      (node (ref "X-NORTH") (pin "99") (pinfunction "99_99") (pintype "bidirectional"))
    )
    (net (code "154") (name "OUT58_N") (class "Default")
      (node (ref "X-NORTH") (pin "94") (pinfunction "94_94") (pintype "bidirectional"))
    )
    (net (code "155") (name "OUT58_P") (class "Default")
      (node (ref "X-NORTH") (pin "96") (pinfunction "96_96") (pintype "bidirectional"))
    )
    (net (code "156") (name "OUT59_N") (class "Default")
      (node (ref "X-EAST") (pin "27") (pinfunction "27_27") (pintype "bidirectional"))
      (node (ref "X-NORTH") (pin "103") (pinfunction "103_103") (pintype "bidirectional"))
    )
    (net (code "157") (name "OUT59_P") (class "Default")
      (node (ref "X-EAST") (pin "25") (pinfunction "25_25") (pintype "bidirectional"))
      (node (ref "X-NORTH") (pin "105") (pinfunction "105_105") (pintype "bidirectional"))
    )
    (net (code "158") (name "OUT60_N") (class "Default")
      (node (ref "X-NORTH") (pin "109") (pinfunction "109_109") (pintype "bidirectional"))
    )
    (net (code "159") (name "OUT60_P") (class "Default")
      (node (ref "X-NORTH") (pin "111") (pinfunction "111_111") (pintype "bidirectional"))
    )
    (net (code "160") (name "OUT61_N") (class "Default")
      (node (ref "X-EAST") (pin "36") (pinfunction "36_36") (pintype "bidirectional"))
      (node (ref "X-NORTH") (pin "100") (pinfunction "100_100") (pintype "bidirectional"))
    )
    (net (code "161") (name "OUT61_P") (class "Default")
      (node (ref "X-EAST") (pin "34") (pinfunction "34_34") (pintype "bidirectional"))
      (node (ref "X-NORTH") (pin "102") (pinfunction "102_102") (pintype "bidirectional"))
    )
    (net (code "162") (name "OUT62_N") (class "Default")
      (node (ref "X-NORTH") (pin "115") (pinfunction "115_115") (pintype "bidirectional"))
    )
    (net (code "163") (name "OUT62_P") (class "Default")
      (node (ref "X-NORTH") (pin "117") (pinfunction "117_117") (pintype "bidirectional"))
    )
    (net (code "164") (name "OUT63_N") (class "Default")
      (node (ref "X-EAST") (pin "30") (pinfunction "30_30") (pintype "bidirectional"))
      (node (ref "X-NORTH") (pin "106") (pinfunction "106_106") (pintype "bidirectional"))
    )
    (net (code "165") (name "OUT63_P") (class "Default")
      (node (ref "X-EAST") (pin "28") (pinfunction "28_28") (pintype "bidirectional"))
      (node (ref "X-NORTH") (pin "108") (pinfunction "108_108") (pintype "bidirectional"))
    )
    (net (code "166") (name "OUT64_N") (class "Default")
      (node (ref "X-NORTH") (pin "112") (pinfunction "112_112") (pintype "bidirectional"))
    )
    (net (code "167") (name "OUT64_P") (class "Default")
      (node (ref "X-NORTH") (pin "114") (pinfunction "114_114") (pintype "bidirectional"))
    )
    (net (code "168") (name "OUTCLK_N") (class "Default")
      (node (ref "X-NORTH") (pin "16") (pinfunction "16_16") (pintype "bidirectional"))
      (node (ref "X-WEST") (pin "53") (pinfunction "53_53") (pintype "bidirectional"))
    )
    (net (code "169") (name "OUTCLK_P") (class "Default")
      (node (ref "X-NORTH") (pin "18") (pinfunction "18_18") (pintype "bidirectional"))
      (node (ref "X-WEST") (pin "55") (pinfunction "55_55") (pintype "bidirectional"))
    )
    (net (code "170") (name "OUTCTR_N") (class "Default")
      (node (ref "X-SOUTH") (pin "126") (pinfunction "126_126") (pintype "bidirectional"))
      (node (ref "X-WEST") (pin "22") (pinfunction "22_22") (pintype "bidirectional"))
    )
    (net (code "171") (name "OUTCTR_P") (class "Default")
      (node (ref "X-SOUTH") (pin "124") (pinfunction "124_124") (pintype "bidirectional"))
      (node (ref "X-WEST") (pin "24") (pinfunction "24_24") (pintype "bidirectional"))
    )
    (net (code "172") (name "S00_N") (class "Default")
      (node (ref "X-SOUTH") (pin "15") (pinfunction "15_15") (pintype "bidirectional"))
    )
    (net (code "173") (name "S00_P") (class "Default")
      (node (ref "X-SOUTH") (pin "13") (pinfunction "13_13") (pintype "bidirectional"))
    )
    (net (code "174") (name "S01_N") (class "Default")
      (node (ref "X-SOUTH") (pin "18") (pinfunction "18_18") (pintype "bidirectional"))
    )
    (net (code "175") (name "S01_P") (class "Default")
      (node (ref "X-SOUTH") (pin "16") (pinfunction "16_16") (pintype "bidirectional"))
    )
    (net (code "176") (name "S02_N") (class "Default")
      (node (ref "X-SOUTH") (pin "21") (pinfunction "21_21") (pintype "bidirectional"))
    )
    (net (code "177") (name "S02_P") (class "Default")
      (node (ref "X-SOUTH") (pin "19") (pinfunction "19_19") (pintype "bidirectional"))
    )
    (net (code "178") (name "S03_N") (class "Default")
      (node (ref "X-SOUTH") (pin "24") (pinfunction "24_24") (pintype "bidirectional"))
    )
    (net (code "179") (name "S03_P") (class "Default")
      (node (ref "X-SOUTH") (pin "22") (pinfunction "22_22") (pintype "bidirectional"))
    )
    (net (code "180") (name "S05_N") (class "Default")
      (node (ref "X-SOUTH") (pin "30") (pinfunction "30_30") (pintype "bidirectional"))
    )
    (net (code "181") (name "S05_P") (class "Default")
      (node (ref "X-SOUTH") (pin "28") (pinfunction "28_28") (pintype "bidirectional"))
    )
    (net (code "182") (name "S38_N") (class "Default")
      (node (ref "X-SOUTH") (pin "129") (pinfunction "129_129") (pintype "bidirectional"))
    )
    (net (code "183") (name "S38_P") (class "Default")
      (node (ref "X-SOUTH") (pin "127") (pinfunction "127_127") (pintype "bidirectional"))
    )
    (net (code "184") (name "S39_N") (class "Default")
      (node (ref "X-SOUTH") (pin "132") (pinfunction "132_132") (pintype "bidirectional"))
    )
    (net (code "185") (name "S39_P") (class "Default")
      (node (ref "X-SOUTH") (pin "130") (pinfunction "130_130") (pintype "bidirectional"))
    )
    (net (code "186") (name "SPI_EN") (class "Default")
      (node (ref "X-EAST") (pin "14") (pinfunction "14_14") (pintype "bidirectional"))
      (node (ref "X-NORTH") (pin "120") (pinfunction "120_120") (pintype "bidirectional"))
    )
    (net (code "187") (name "SYS_RES_N") (class "Default")
      (node (ref "X-EAST") (pin "22") (pinfunction "22_22") (pintype "bidirectional"))
      (node (ref "X-NORTH") (pin "126") (pinfunction "126_126") (pintype "bidirectional"))
    )
    (net (code "188") (name "S_CHK_V") (class "Default")
      (node (ref "X-EAST") (pin "92") (pinfunction "92_92") (pintype "bidirectional"))
      (node (ref "X-EAST") (pin "94") (pinfunction "94_94") (pintype "bidirectional"))
      (node (ref "X-SOUTH") (pin "7") (pinfunction "7_7") (pintype "bidirectional"))
      (node (ref "X-SOUTH") (pin "9") (pinfunction "9_9") (pintype "bidirectional"))
    )
    (net (code "189") (name "S_I2C_V") (class "Default")
      (node (ref "X-SOUTH") (pin "136") (pinfunction "136_136") (pintype "bidirectional"))
      (node (ref "X-SOUTH") (pin "138") (pinfunction "138_138") (pintype "bidirectional"))
      (node (ref "X-WEST") (pin "7") (pinfunction "7_7") (pintype "bidirectional"))
      (node (ref "X-WEST") (pin "9") (pinfunction "9_9") (pintype "bidirectional"))
    )
    (net (code "190") (name "S_SCK") (class "Default")
      (node (ref "X-SOUTH") (pin "143") (pinfunction "143_143") (pintype "bidirectional"))
      (node (ref "X-WEST") (pin "2") (pinfunction "2_2") (pintype "bidirectional"))
    )
    (net (code "191") (name "S_SCL") (class "Default")
      (node (ref "X-SOUTH") (pin "144") (pinfunction "144_144") (pintype "bidirectional"))
      (node (ref "X-WEST") (pin "1") (pinfunction "1_1") (pintype "bidirectional"))
    )
    (net (code "192") (name "S_SDA") (class "Default")
      (node (ref "X-SOUTH") (pin "142") (pinfunction "142_142") (pintype "bidirectional"))
      (node (ref "X-WEST") (pin "3") (pinfunction "3_3") (pintype "bidirectional"))
    )
    (net (code "193") (name "S_SDI") (class "Default")
      (node (ref "X-SOUTH") (pin "139") (pinfunction "139_139") (pintype "bidirectional"))
      (node (ref "X-WEST") (pin "6") (pinfunction "6_6") (pintype "bidirectional"))
    )
    (net (code "194") (name "S_SDO") (class "Default")
      (node (ref "X-SOUTH") (pin "141") (pinfunction "141_141") (pintype "bidirectional"))
      (node (ref "X-WEST") (pin "4") (pinfunction "4_4") (pintype "bidirectional"))
    )
    (net (code "195") (name "S_SPI_V") (class "Default")
      (node (ref "X-SOUTH") (pin "133") (pinfunction "133_133") (pintype "bidirectional"))
      (node (ref "X-SOUTH") (pin "135") (pinfunction "135_135") (pintype "bidirectional"))
      (node (ref "X-WEST") (pin "10") (pinfunction "10_10") (pintype "bidirectional"))
      (node (ref "X-WEST") (pin "8") (pinfunction "8_8") (pintype "bidirectional"))
    )
    (net (code "196") (name "S_VE") (class "Default")
      (node (ref "P-E") (pin "5") (pinfunction "5_5") (pintype "passive"))
      (node (ref "X-EAST") (pin "51") (pinfunction "51_51") (pintype "bidirectional"))
      (node (ref "X-EAST") (pin "57") (pinfunction "57_57") (pintype "bidirectional"))
      (node (ref "X-EAST") (pin "63") (pinfunction "63_63") (pintype "bidirectional"))
      (node (ref "X-EAST") (pin "69") (pinfunction "69_69") (pintype "bidirectional"))
      (node (ref "X-SOUTH") (pin "14") (pinfunction "14_14") (pintype "bidirectional"))
      (node (ref "X-SOUTH") (pin "20") (pinfunction "20_20") (pintype "bidirectional"))
      (node (ref "X-SOUTH") (pin "26") (pinfunction "26_26") (pintype "bidirectional"))
      (node (ref "X-SOUTH") (pin "32") (pinfunction "32_32") (pintype "bidirectional"))
      (node (ref "X-SOUTH") (pin "38") (pinfunction "38_38") (pintype "bidirectional"))
    )
    (net (code "197") (name "S_VE_CV") (class "Default")
      (node (ref "X-EAST") (pin "100") (pinfunction "100_100") (pintype "bidirectional"))
      (node (ref "X-SOUTH") (pin "1") (pinfunction "1_1") (pintype "bidirectional"))
    )
    (net (code "198") (name "S_VE_OV") (class "Default")
      (node (ref "X-EAST") (pin "99") (pinfunction "99_99") (pintype "bidirectional"))
      (node (ref "X-SOUTH") (pin "2") (pinfunction "2_2") (pintype "bidirectional"))
    )
    (net (code "199") (name "S_VE_UV") (class "Default")
      (node (ref "X-EAST") (pin "89") (pinfunction "89_89") (pintype "bidirectional"))
      (node (ref "X-SOUTH") (pin "8") (pinfunction "8_8") (pintype "bidirectional"))
    )
    (net (code "200") (name "S_VS") (class "Default")
      (node (ref "P-E") (pin "3") (pinfunction "3_3") (pintype "passive"))
      (node (ref "X-EAST") (pin "32") (pinfunction "32_32") (pintype "bidirectional"))
      (node (ref "X-EAST") (pin "38") (pinfunction "38_38") (pintype "bidirectional"))
      (node (ref "X-EAST") (pin "44") (pinfunction "44_44") (pintype "bidirectional"))
      (node (ref "X-EAST") (pin "50") (pinfunction "50_50") (pintype "bidirectional"))
      (node (ref "X-EAST") (pin "52") (pinfunction "52_52") (pintype "bidirectional"))
      (node (ref "X-EAST") (pin "58") (pinfunction "58_58") (pintype "bidirectional"))
      (node (ref "X-EAST") (pin "64") (pinfunction "64_64") (pintype "bidirectional"))
      (node (ref "X-EAST") (pin "70") (pinfunction "70_70") (pintype "bidirectional"))
      (node (ref "X-SOUTH") (pin "50") (pinfunction "50_50") (pintype "bidirectional"))
      (node (ref "X-SOUTH") (pin "56") (pinfunction "56_56") (pintype "bidirectional"))
      (node (ref "X-SOUTH") (pin "62") (pinfunction "62_62") (pintype "bidirectional"))
      (node (ref "X-SOUTH") (pin "68") (pinfunction "68_68") (pintype "bidirectional"))
      (node (ref "X-SOUTH") (pin "74") (pinfunction "74_74") (pintype "bidirectional"))
      (node (ref "X-SOUTH") (pin "80") (pinfunction "80_80") (pintype "bidirectional"))
      (node (ref "X-SOUTH") (pin "86") (pinfunction "86_86") (pintype "bidirectional"))
      (node (ref "X-SOUTH") (pin "92") (pinfunction "92_92") (pintype "bidirectional"))
      (node (ref "X-SOUTH") (pin "98") (pinfunction "98_98") (pintype "bidirectional"))
    )
    (net (code "201") (name "S_VS_CV") (class "Default")
      (node (ref "X-EAST") (pin "98") (pinfunction "98_98") (pintype "bidirectional"))
      (node (ref "X-SOUTH") (pin "3") (pinfunction "3_3") (pintype "bidirectional"))
    )
    (net (code "202") (name "S_VS_OV") (class "Default")
      (node (ref "X-EAST") (pin "97") (pinfunction "97_97") (pintype "bidirectional"))
      (node (ref "X-SOUTH") (pin "4") (pinfunction "4_4") (pintype "bidirectional"))
    )
    (net (code "203") (name "S_VS_UV") (class "Default")
      (node (ref "X-EAST") (pin "87") (pinfunction "87_87") (pintype "bidirectional"))
      (node (ref "X-SOUTH") (pin "10") (pinfunction "10_10") (pintype "bidirectional"))
    )
    (net (code "204") (name "S_VW") (class "Default")
      (node (ref "P-W") (pin "1") (pinfunction "1_1") (pintype "passive"))
      (node (ref "X-SOUTH") (pin "110") (pinfunction "110_110") (pintype "bidirectional"))
      (node (ref "X-SOUTH") (pin "116") (pinfunction "116_116") (pintype "bidirectional"))
      (node (ref "X-SOUTH") (pin "122") (pinfunction "122_122") (pintype "bidirectional"))
      (node (ref "X-SOUTH") (pin "128") (pinfunction "128_128") (pintype "bidirectional"))
      (node (ref "X-SOUTH") (pin "134") (pinfunction "134_134") (pintype "bidirectional"))
      (node (ref "X-WEST") (pin "31") (pinfunction "31_31") (pintype "bidirectional"))
      (node (ref "X-WEST") (pin "37") (pinfunction "37_37") (pintype "bidirectional"))
      (node (ref "X-WEST") (pin "43") (pinfunction "43_43") (pintype "bidirectional"))
      (node (ref "X-WEST") (pin "49") (pinfunction "49_49") (pintype "bidirectional"))
    )
    (net (code "205") (name "S_VW_CV") (class "Default")
      (node (ref "X-EAST") (pin "96") (pinfunction "96_96") (pintype "bidirectional"))
      (node (ref "X-SOUTH") (pin "5") (pinfunction "5_5") (pintype "bidirectional"))
    )
    (net (code "206") (name "S_VW_OV") (class "Default")
      (node (ref "X-EAST") (pin "95") (pinfunction "95_95") (pintype "bidirectional"))
      (node (ref "X-SOUTH") (pin "6") (pinfunction "6_6") (pintype "bidirectional"))
    )
    (net (code "207") (name "S_VW_UV") (class "Default")
      (node (ref "X-EAST") (pin "85") (pinfunction "85_85") (pintype "bidirectional"))
      (node (ref "X-SOUTH") (pin "12") (pinfunction "12_12") (pintype "bidirectional"))
    )
    (net (code "208") (name "TCK") (class "Default")
      (node (ref "X-WEST") (pin "12") (pinfunction "12_12") (pintype "bidirectional"))
    )
    (net (code "209") (name "TDI") (class "Default")
      (node (ref "X-WEST") (pin "16") (pinfunction "16_16") (pintype "bidirectional"))
    )
    (net (code "210") (name "TDIG1") (class "Default")
      (node (ref "X-EAST") (pin "18") (pinfunction "18_18") (pintype "bidirectional"))
      (node (ref "X-NORTH") (pin "124") (pinfunction "124_124") (pintype "bidirectional"))
    )
    (net (code "211") (name "TDIG2") (class "Default")
      (node (ref "X-EAST") (pin "17") (pinfunction "17_17") (pintype "bidirectional"))
      (node (ref "X-NORTH") (pin "129") (pinfunction "129_129") (pintype "bidirectional"))
    )
    (net (code "212") (name "TDO") (class "Default")
      (node (ref "X-WEST") (pin "18") (pinfunction "18_18") (pintype "bidirectional"))
    )
    (net (code "213") (name "TMS") (class "Default")
      (node (ref "X-WEST") (pin "14") (pinfunction "14_14") (pintype "bidirectional"))
    )
    (net (code "214") (name "T_EXP1") (class "Default")
      (node (ref "X-EAST") (pin "12") (pinfunction "12_12") (pintype "bidirectional"))
      (node (ref "X-NORTH") (pin "132") (pinfunction "132_132") (pintype "bidirectional"))
    )
    (net (code "215") (name "T_EXP2") (class "Default")
      (node (ref "X-EAST") (pin "16") (pinfunction "16_16") (pintype "bidirectional"))
      (node (ref "X-NORTH") (pin "118") (pinfunction "118_118") (pintype "bidirectional"))
    )
    (net (code "216") (name "W_I2C_V") (class "Default")
      (node (ref "X-WEST") (pin "11") (pinfunction "11_11") (pintype "bidirectional"))
      (node (ref "X-WEST") (pin "13") (pinfunction "13_13") (pintype "bidirectional"))
    )
    (net (code "217") (name "W_SCL") (class "Default")
      (node (ref "X-WEST") (pin "15") (pinfunction "15_15") (pintype "bidirectional"))
    )
    (net (code "218") (name "W_SDA") (class "Default")
      (node (ref "X-WEST") (pin "17") (pinfunction "17_17") (pintype "bidirectional"))
    )
    (net (code "219") (name "W_VW") (class "Default")
      (node (ref "X-WEST") (pin "79") (pinfunction "79_79") (pintype "bidirectional"))
      (node (ref "X-WEST") (pin "81") (pinfunction "81_81") (pintype "bidirectional"))
      (node (ref "X-WEST") (pin "83") (pinfunction "83_83") (pintype "bidirectional"))
      (node (ref "X-WEST") (pin "84") (pinfunction "84_84") (pintype "bidirectional"))
      (node (ref "X-WEST") (pin "86") (pinfunction "86_86") (pintype "bidirectional"))
      (node (ref "X-WEST") (pin "88") (pinfunction "88_88") (pintype "bidirectional"))
    )
    (net (code "220") (name "W_VW_CV") (class "Default")
      (node (ref "X-WEST") (pin "90") (pinfunction "90_90") (pintype "bidirectional"))
    )
    (net (code "221") (name "W_VW_OV") (class "Default")
      (node (ref "X-WEST") (pin "93") (pinfunction "93_93") (pintype "bidirectional"))
    )
    (net (code "222") (name "W_VW_UV") (class "Default")
      (node (ref "X-WEST") (pin "91") (pinfunction "91_91") (pintype "bidirectional"))
    )
    (net (code "223") (name "unconnected-(X-EAST-PadM1)") (class "Default")
      (node (ref "X-EAST") (pin "M1") (pinfunction "M1_M1") (pintype "bidirectional"))
    )
    (net (code "224") (name "unconnected-(X-EAST-PadM2)") (class "Default")
      (node (ref "X-EAST") (pin "M2") (pinfunction "M2_M2") (pintype "bidirectional"))
    )
    (net (code "225") (name "unconnected-(X-NORTH-PadM1)") (class "Default")
      (node (ref "X-NORTH") (pin "M1") (pinfunction "M1_M1") (pintype "bidirectional"))
    )
    (net (code "226") (name "unconnected-(X-NORTH-PadM2)") (class "Default")
      (node (ref "X-NORTH") (pin "M2") (pinfunction "M2_M2") (pintype "bidirectional"))
    )
    (net (code "227") (name "unconnected-(X-SOUTH-PadM1)") (class "Default")
      (node (ref "X-SOUTH") (pin "M1") (pinfunction "M1_M1") (pintype "bidirectional"))
    )
    (net (code "228") (name "unconnected-(X-SOUTH-PadM2)") (class "Default")
      (node (ref "X-SOUTH") (pin "M2") (pinfunction "M2_M2") (pintype "bidirectional"))
    )
    (net (code "229") (name "unconnected-(X-WEST-PadM1)") (class "Default")
      (node (ref "X-WEST") (pin "M1") (pinfunction "M1_M1") (pintype "bidirectional"))
    )
    (net (code "230") (name "unconnected-(X-WEST-PadM2)") (class "Default")
      (node (ref "X-WEST") (pin "M2") (pinfunction "M2_M2") (pintype "bidirectional"))
    )
  )
)
